# power.net
KiCad netlist of a schematic drawn in Altium Designer
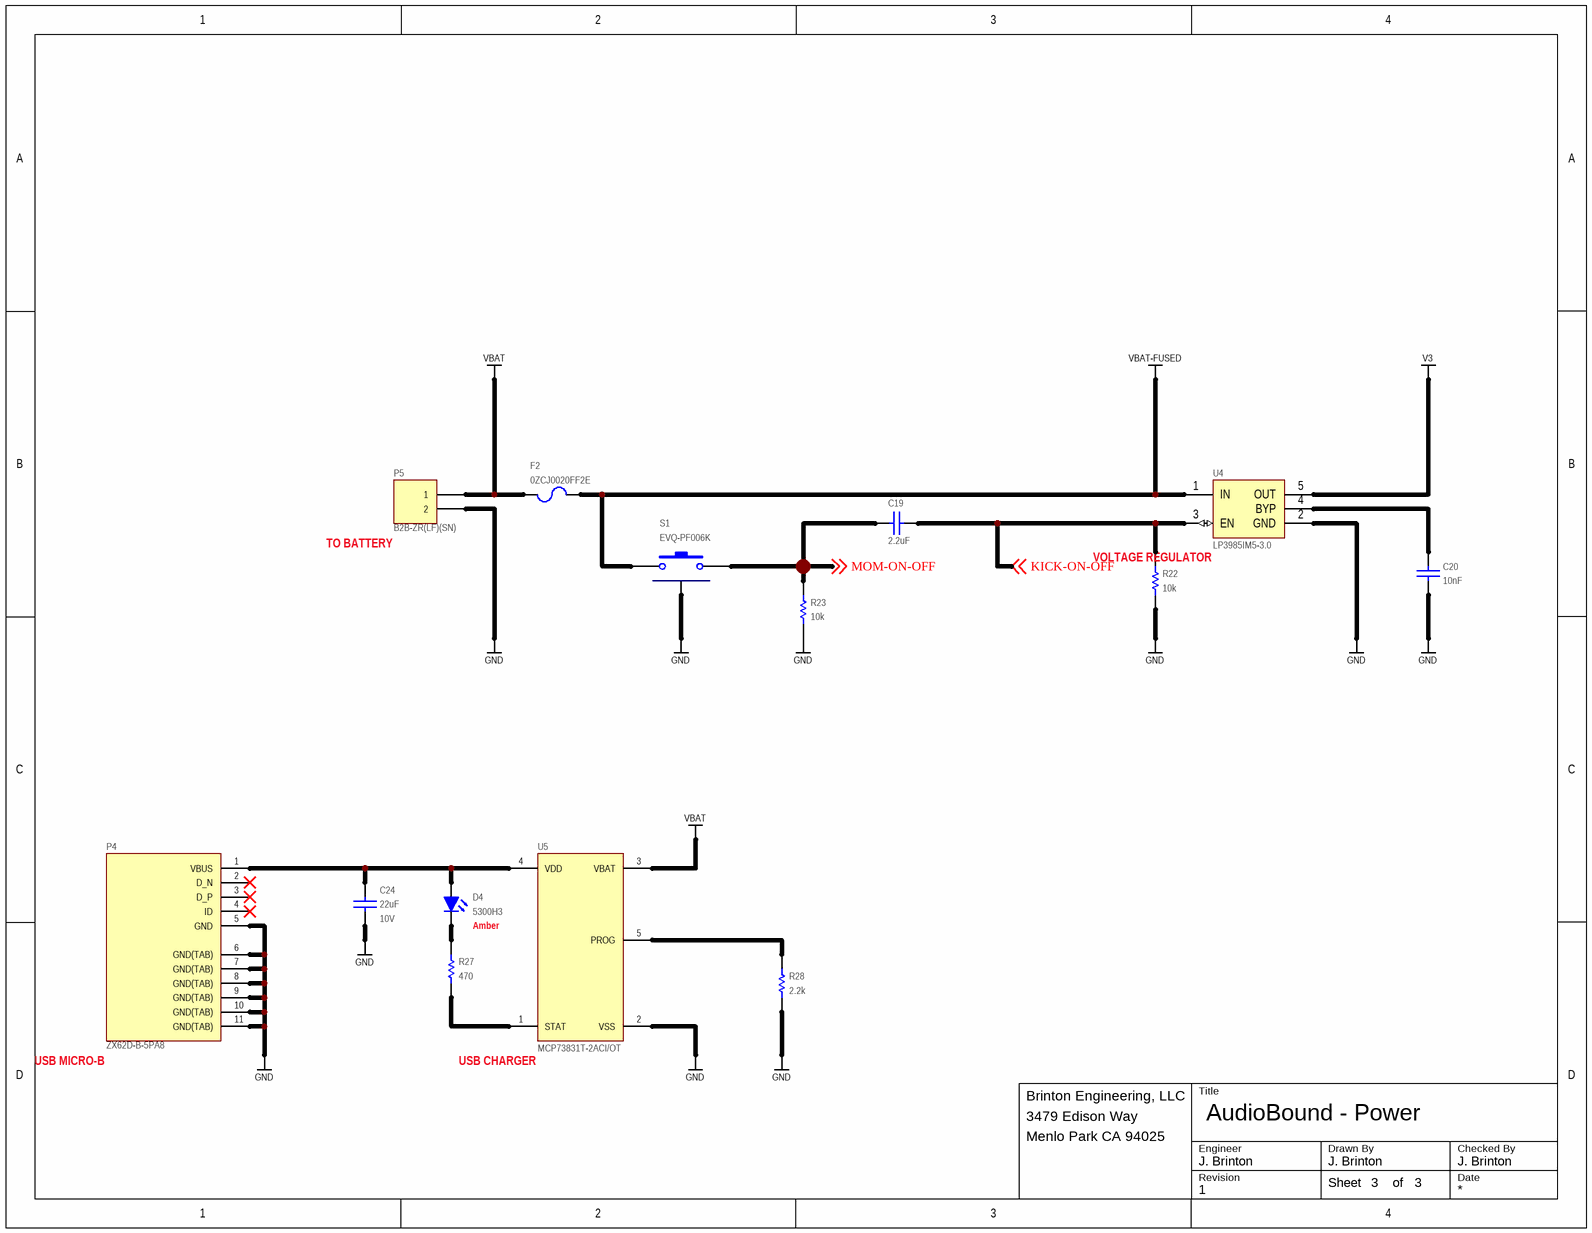
[diagram p0: power.SchDoc]

(export (version "E")
  (design (tool "Eeschema 10.0.6"))
  (components
    (comp (ref "C19")
      (value "2.2uF")
      (footprint "CAPC160X80X90L20N")
      (description "Ceramic Capacitor 2.2uF ±20% 10V X7R 0603")
      (fields (field (name "TOLERANCE") "±20%") (field (name "MANUFACTURER") "TDK"))
      (libsource (lib "generic") (part "Cap"))
    )
    (comp (ref "C20")
      (value "10nF")
      (footprint "CAPC100X50X55L25N")
      (description "Ceramic Capacitor 10nF ±10% 50V X7R 0402")
      (fields (field (name "TOLERANCE") "±10%") (field (name "MANUFACTURER") "Murata"))
      (libsource (lib "generic") (part "Cap"))
    )
    (comp (ref "C24")
      (value "22uF")
      (footprint "CAPC200X125X145L45N")
      (description "Ceramic Capacitor 22uF ±20% 10V X7S 0805")
      (fields
        (field (name "MANUFACTURER") "TDK")
        (field (name "TOLERANCE") "±20%")
        (field (name "VOLTAGE") "10V")
      )
      (libsource (lib "generic") (part "CAP"))
    )
    (comp (ref "D4")
      (value "5300H3")
      (footprint "5300Hx")
      (description "LED, Color Amber, 10mA, 2.0V")
      (fields (field (name "MANUFACTURER") "Visual Communications Company"))
      (libsource (lib "generic") (part "LED0603RD"))
    )
    (comp (ref "F2")
      (value "0ZCJ0020FF2E")
      (footprint "generic:1206")
      (description "PTC Resettable Fuse, 0.2A, 30V, SMD 1206")
      (fields (field (name "MANUFACTURER") "Bell Fuse"))
      (libsource (lib "bel-fuse") (part "0ZCJ0020FF2E"))
    )
    (comp (ref "P4")
      (value "ZX62D-B-5PA8")
      (footprint "hirose:ZX62D-B-5PA8")
      (description "USB Micro-B SMD Connector")
      (fields (field (name "MANUFACTURER") "Hirose"))
      (libsource (lib "hirose") (part "ZX62D-B-5PA8"))
    )
    (comp (ref "P5")
      (value "B2B-ZR(LF)(SN)")
      (footprint "B2B-ZR")
      (description "Header, 2-Pin")
      (fields (field (name "MANUFACTURER") "JST"))
      (libsource (lib "Miscellaneous Connectors") (part "Header 2"))
    )
    (comp (ref "R22")
      (value "10k")
      (footprint "RESC1005X40N")
      (description "Thick Film Resistor 10k ±1% 0.1W 50V 0402")
      (fields (field (name "MANUFACTURER") "Panasonic") (field (name "TOLERANCE") "±1%"))
      (libsource (lib "generic") (part "RES"))
    )
    (comp (ref "R23")
      (value "10k")
      (footprint "RESC1005X40N")
      (description "Thick Film Resistor 10k ±1% 0.1W 50V 0402")
      (fields (field (name "MANUFACTURER") "Panasonic") (field (name "TOLERANCE") "±1%"))
      (libsource (lib "generic") (part "RES"))
    )
    (comp (ref "R27")
      (value "470")
      (footprint "RESC1005X40N")
      (description "Thick Film Resistor 470 ±1% 0.1W 50V 0402")
      (fields (field (name "MANUFACTURER") "Panasonic") (field (name "TOLERANCE") "±1%"))
      (libsource (lib "generic") (part "RES"))
    )
    (comp (ref "R28")
      (value "2.2k")
      (footprint "RESC1005X40N")
      (description "Thick Film Resistor 2.2k ±1% 0.1W 50V 0402")
      (fields (field (name "MANUFACTURER") "Panasonic") (field (name "TOLERANCE") "±1%"))
      (libsource (lib "generic") (part "RES"))
    )
    (comp (ref "S1")
      (value "EVQ-PF006K")
      (footprint "EVQ-PF006K")
      (description "Tactile Switch; Normally Open")
      (fields (field (name "MANUFACTURER") "Panasonic"))
      (libsource (lib "panasonic") (part "EVQ-PF006K"))
    )
    (comp (ref "U4")
      (value "LP3985IM5-3.0")
      (footprint "DBV-5")
      (description "Low Dropout Regulator, Fixed, 150mA, 30uV Low Noise, 3.0V")
      (fields (field (name "MANUFACTURER") "Texas Instruments") (field (name "VOLTAGE") "3.0V"))
      (libsource (lib "ti") (part "LP3985IM5-2.5"))
    )
    (comp (ref "U5")
      (value "MCP73831T-2ACI/OT")
      (footprint "SOT23-5")
      (description "Single-Cell LiPo Charger")
      (fields (field (name "MANUFACTURER") "Microchip"))
      (libsource (lib "microchip") (part "MCP73831T-2ACI/OT"))
    )
  )
  (nets
    (net (code "1") (name "GND") (class "Default")
      (node (ref "C20") (pin "1") (pinfunction "1_1") (pintype "passive"))
      (node (ref "C24") (pin "2") (pinfunction "2_2") (pintype "passive"))
      (node (ref "P4") (pin "10") (pinfunction "GND(TAB)_10") (pintype "passive"))
      (node (ref "P4") (pin "11") (pinfunction "GND(TAB)_11") (pintype "passive"))
      (node (ref "P4") (pin "5") (pinfunction "GND_5") (pintype "passive"))
      (node (ref "P4") (pin "6") (pinfunction "GND(TAB)_6") (pintype "passive"))
      (node (ref "P4") (pin "7") (pinfunction "GND(TAB)_7") (pintype "passive"))
      (node (ref "P4") (pin "8") (pinfunction "GND(TAB)_8") (pintype "passive"))
      (node (ref "P4") (pin "9") (pinfunction "GND(TAB)_9") (pintype "passive"))
      (node (ref "P5") (pin "2") (pinfunction "2_2") (pintype "passive"))
      (node (ref "R22") (pin "1") (pinfunction "1_1") (pintype "passive"))
      (node (ref "R23") (pin "2") (pinfunction "2_2") (pintype "passive"))
      (node (ref "R28") (pin "2") (pinfunction "2_2") (pintype "passive"))
      (node (ref "S1") (pin "3") (pinfunction "3_3") (pintype "passive"))
      (node (ref "U4") (pin "2") (pinfunction "GND_2") (pintype "power_in"))
      (node (ref "U5") (pin "2") (pinfunction "VSS_2") (pintype "passive"))
    )
    (net (code "2") (name "KICK-ON-OFF") (class "Default")
      (node (ref "C19") (pin "1") (pinfunction "1_1") (pintype "passive"))
      (node (ref "R22") (pin "2") (pinfunction "2_2") (pintype "passive"))
      (node (ref "U4") (pin "3") (pinfunction "EN_3") (pintype "bidirectional"))
    )
    (net (code "3") (name "MOM-ON-OFF") (class "Default")
      (node (ref "C19") (pin "2") (pinfunction "2_2") (pintype "passive"))
      (node (ref "R23") (pin "1") (pinfunction "1_1") (pintype "passive"))
      (node (ref "S1") (pin "2") (pinfunction "2_2") (pintype "passive"))
    )
    (net (code "4") (name "Net-(D4-A)") (class "Default")
      (node (ref "C24") (pin "1") (pinfunction "1_1") (pintype "passive"))
      (node (ref "D4") (pin "1") (pinfunction "A_1") (pintype "passive"))
      (node (ref "P4") (pin "1") (pinfunction "VBUS_1") (pintype "passive"))
      (node (ref "U5") (pin "4") (pinfunction "VDD_4") (pintype "passive"))
    )
    (net (code "5") (name "Net-(D4-K)") (class "Default")
      (node (ref "D4") (pin "2") (pinfunction "K_2") (pintype "passive"))
      (node (ref "R27") (pin "1") (pinfunction "1_1") (pintype "passive"))
    )
    (net (code "6") (name "Net-(U4-BYP)") (class "Default")
      (node (ref "C20") (pin "2") (pinfunction "2_2") (pintype "passive"))
      (node (ref "U4") (pin "4") (pinfunction "BYP_4") (pintype "passive"))
    )
    (net (code "7") (name "Net-(U5-PROG)") (class "Default")
      (node (ref "R28") (pin "1") (pinfunction "1_1") (pintype "passive"))
      (node (ref "U5") (pin "5") (pinfunction "PROG_5") (pintype "passive"))
    )
    (net (code "8") (name "Net-(U5-STAT)") (class "Default")
      (node (ref "R27") (pin "2") (pinfunction "2_2") (pintype "passive"))
      (node (ref "U5") (pin "1") (pinfunction "STAT_1") (pintype "passive"))
    )
    (net (code "9") (name "V3") (class "Default")
      (node (ref "U4") (pin "5") (pinfunction "OUT_5") (pintype "power_in"))
    )
    (net (code "10") (name "VBAT") (class "Default")
      (node (ref "F2") (pin "2") (pinfunction "2_2") (pintype "passive"))
      (node (ref "P5") (pin "1") (pinfunction "1_1") (pintype "passive"))
      (node (ref "U5") (pin "3") (pinfunction "VBAT_3") (pintype "passive"))
    )
    (net (code "11") (name "VBAT-FUSED") (class "Default")
      (node (ref "F2") (pin "1") (pinfunction "1_1") (pintype "passive"))
      (node (ref "S1") (pin "1") (pinfunction "1_1") (pintype "passive"))
      (node (ref "U4") (pin "1") (pinfunction "IN_1") (pintype "power_in"))
    )
    (net (code "12") (name "unconnected-(P4-D_N-Pad2)") (class "Default")
      (node (ref "P4") (pin "2") (pinfunction "D_N_2") (pintype "passive+no_connect"))
    )
    (net (code "13") (name "unconnected-(P4-D_P-Pad3)") (class "Default")
      (node (ref "P4") (pin "3") (pinfunction "D_P_3") (pintype "passive+no_connect"))
    )
    (net (code "14") (name "unconnected-(P4-ID-Pad4)") (class "Default")
      (node (ref "P4") (pin "4") (pinfunction "ID_4") (pintype "passive+no_connect"))
    )
  )
)
